# SArduino.net
KiCad netlist of a schematic drawn in EAGLE
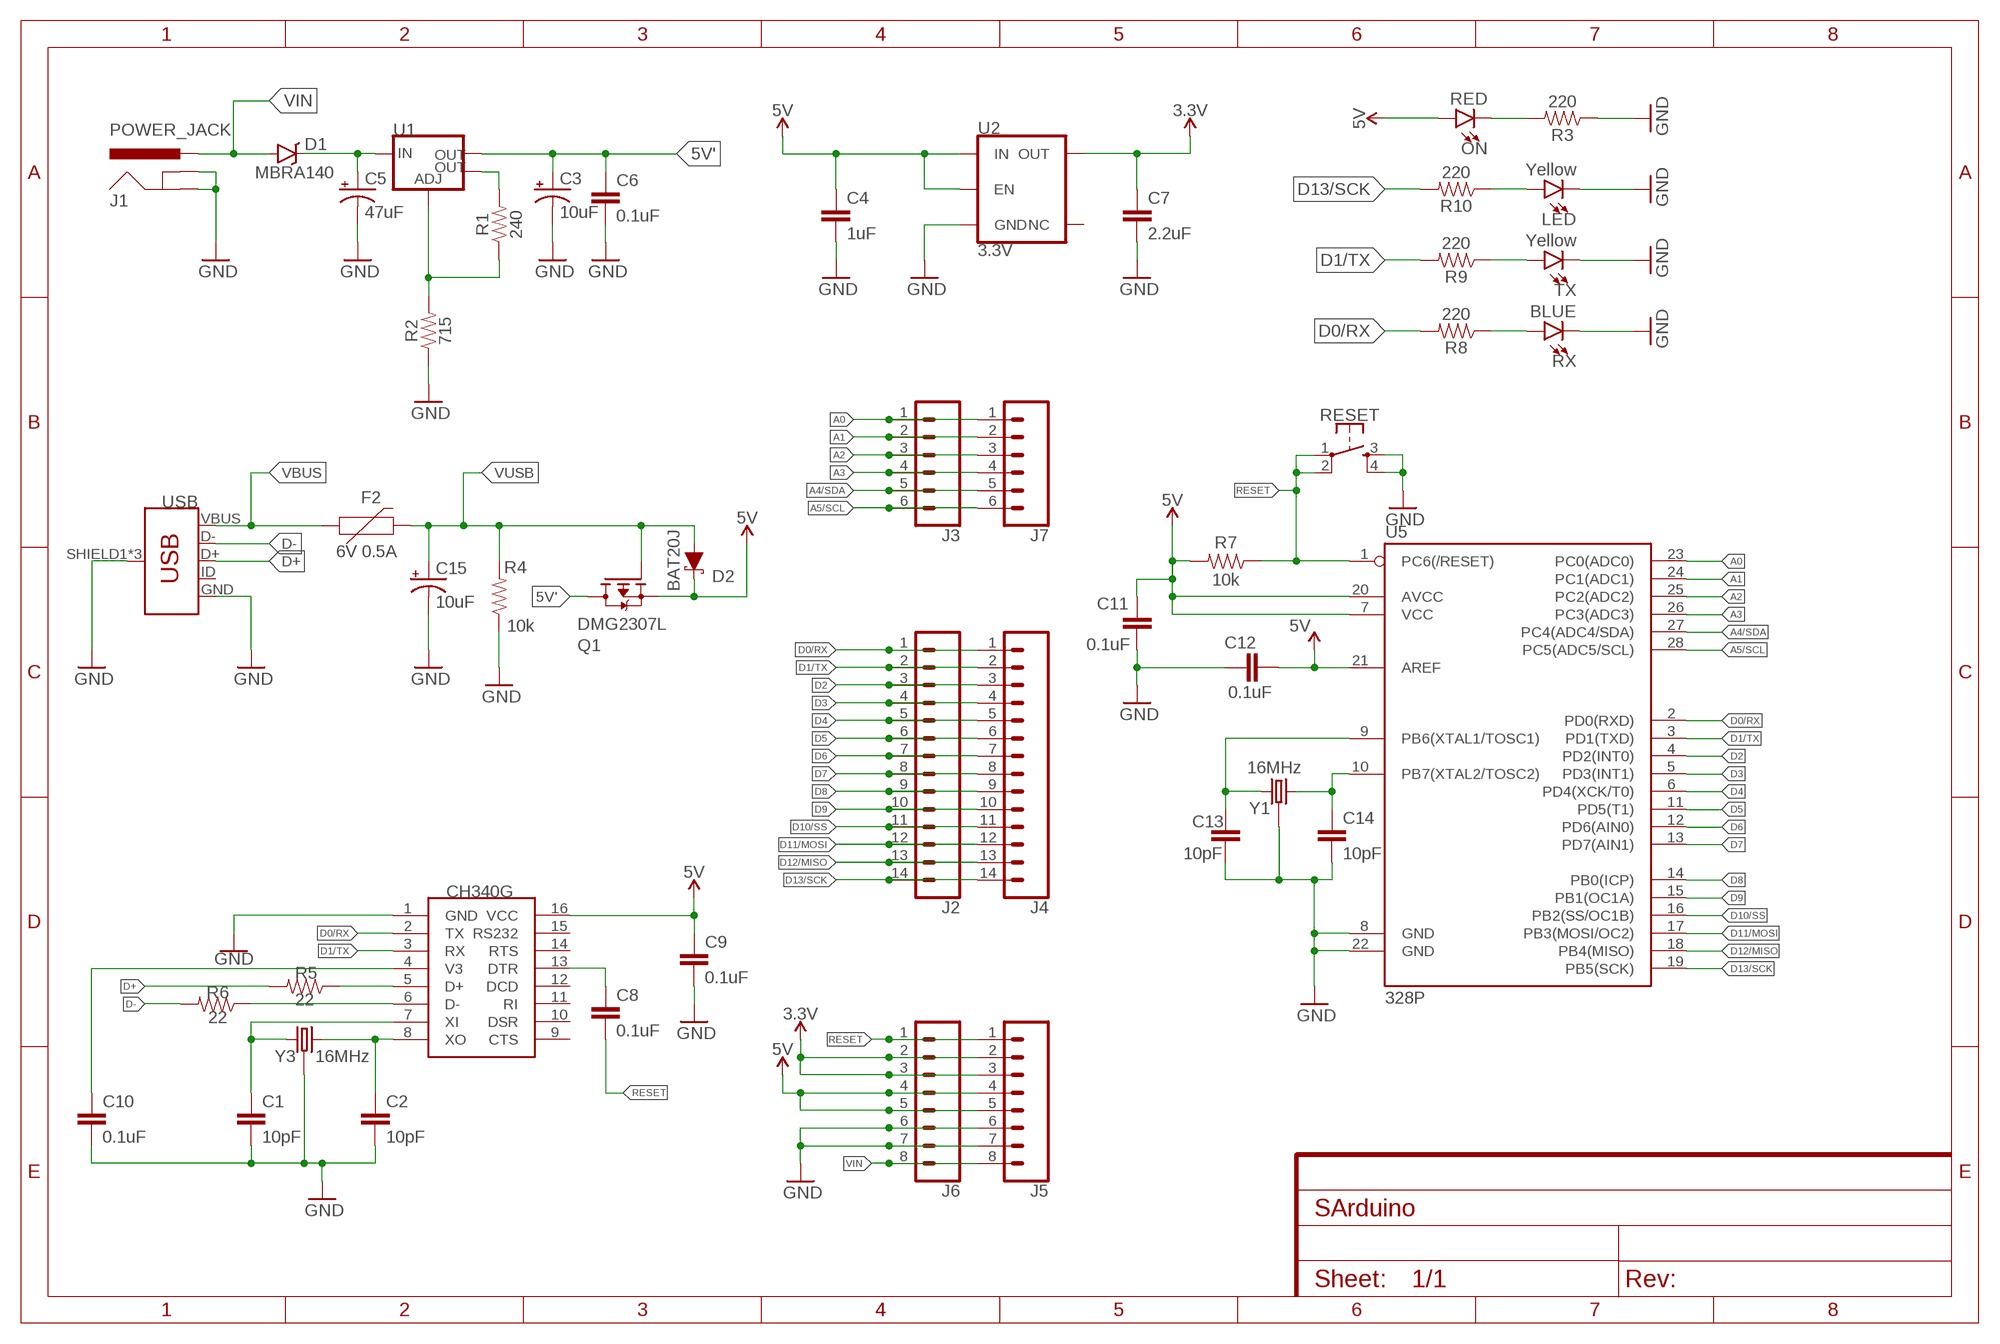
[diagram p0: schematic, sheet 1]

(export (version "E")
  (design (tool "Eeschema 10.0.6"))
  (components
    (comp (ref "C1")
      (value "10pF")
      (footprint "eagle-import:0603")
      (libsource (lib "eagle-import") (part "0.1UF-0603-25V-(+80/-20%)"))
    )
    (comp (ref "C2")
      (value "10pF")
      (footprint "eagle-import:0603")
      (libsource (lib "eagle-import") (part "0.1UF-0603-25V-(+80/-20%)"))
    )
    (comp (ref "C3")
      (value "10uF")
      (footprint "eagle-import:EIA3216")
      (libsource (lib "eagle-import") (part "10UF-POLAR-EIA3216-16V-10%(TANT)"))
    )
    (comp (ref "C4")
      (value "1uF")
      (footprint "eagle-import:0603")
      (libsource (lib "eagle-import") (part "0.1UF-0603-25V-(+80/-20%)"))
    )
    (comp (ref "C5")
      (value "47uF")
      (footprint "eagle-import:PANASONIC_D")
      (libsource (lib "eagle-import") (part "47UF-POLAR-PANASONIC_D-35V-20%"))
    )
    (comp (ref "C6")
      (value "0.1uF")
      (footprint "eagle-import:0603")
      (libsource (lib "eagle-import") (part "0.1UF-0603-25V-(+80/-20%)"))
    )
    (comp (ref "C7")
      (value "2.2uF")
      (footprint "eagle-import:0603")
      (libsource (lib "eagle-import") (part "0.1UF-0603-25V-(+80/-20%)"))
    )
    (comp (ref "C8")
      (value "0.1uF")
      (footprint "eagle-import:0603")
      (libsource (lib "eagle-import") (part "0.1UF-0603-25V-(+80/-20%)"))
    )
    (comp (ref "C9")
      (value "0.1uF")
      (footprint "eagle-import:0603")
      (libsource (lib "eagle-import") (part "0.1UF-0603-25V-(+80/-20%)"))
    )
    (comp (ref "C10")
      (value "0.1uF")
      (footprint "eagle-import:0603")
      (libsource (lib "eagle-import") (part "0.1UF-0603-25V-(+80/-20%)"))
    )
    (comp (ref "C11")
      (value "0.1uF")
      (footprint "eagle-import:0603")
      (libsource (lib "eagle-import") (part "0.1UF-0603-25V-(+80/-20%)"))
    )
    (comp (ref "C12")
      (value "0.1uF")
      (footprint "eagle-import:0603")
      (libsource (lib "eagle-import") (part "0.1UF-0603-25V-(+80/-20%)"))
    )
    (comp (ref "C13")
      (value "10pF")
      (footprint "eagle-import:0603")
      (libsource (lib "eagle-import") (part "0.1UF-0603-25V-(+80/-20%)"))
    )
    (comp (ref "C14")
      (value "10pF")
      (footprint "eagle-import:0603")
      (libsource (lib "eagle-import") (part "0.1UF-0603-25V-(+80/-20%)"))
    )
    (comp (ref "C15")
      (value "10uF")
      (footprint "eagle-import:EIA3216")
      (libsource (lib "eagle-import") (part "10UF-POLAR-EIA3216-16V-10%(TANT)"))
    )
    (comp (ref "D1")
      (value "MBRA140")
      (footprint "eagle-import:SMA-DIODE@1")
      (libsource (lib "eagle-import") (part "MBRA140"))
    )
    (comp (ref "D2")
      (value "BAT20J")
      (footprint "eagle-import:SOD-323")
      (libsource (lib "eagle-import") (part "DIODE-SCHOTTKY-BAT20J"))
    )
    (comp (ref "F2")
      (value "6V 0.5A")
      (footprint "eagle-import:0805")
      (libsource (lib "eagle-import") (part "PPTC_6V500MA"))
    )
    (comp (ref "J1")
      (value "POWER_JACK")
      (footprint "eagle-import:POWER_JACK_PTH")
      (libsource (lib "eagle-import") (part "POWER_JACK"))
    )
    (comp (ref "J2")
      (value "CONN_14")
      (footprint "eagle-import:1X14")
      (libsource (lib "eagle-import") (part "CONN_14"))
    )
    (comp (ref "J3")
      (value "CONN_06SILK_FEMALE_PTH")
      (footprint "eagle-import:1X06")
      (libsource (lib "eagle-import") (part "CONN_06SILK_FEMALE_PTH"))
    )
    (comp (ref "J4")
      (value "CONN_14")
      (footprint "eagle-import:1X14")
      (libsource (lib "eagle-import") (part "CONN_14"))
    )
    (comp (ref "J5")
      (value "CONN_08\"")
      (footprint "eagle-import:1X08")
      (libsource (lib "eagle-import") (part "CONN_08{dblquote}"))
    )
    (comp (ref "J6")
      (value "CONN_08\"")
      (footprint "eagle-import:1X08")
      (libsource (lib "eagle-import") (part "CONN_08{dblquote}"))
    )
    (comp (ref "J7")
      (value "CONN_06SILK_FEMALE_PTH")
      (footprint "eagle-import:1X06")
      (libsource (lib "eagle-import") (part "CONN_06SILK_FEMALE_PTH"))
    )
    (comp (ref "LED")
      (value "Yellow")
      (footprint "eagle-import:LED-0603")
      (libsource (lib "eagle-import") (part "LED-YELLOW0603"))
    )
    (comp (ref "ON")
      (value "RED")
      (footprint "eagle-import:LED-0603")
      (libsource (lib "eagle-import") (part "LED-RED0603"))
    )
    (comp (ref "Q1")
      (value "DMG2307L")
      (footprint "eagle-import:SOT96P240X110-3N")
      (fields (field (name "MF") "Diodes Inc."))
      (libsource (lib "eagle-import") (part "DMG2307L"))
    )
    (comp (ref "R1")
      (value "240")
      (footprint "eagle-import:0603")
      (libsource (lib "eagle-import") (part "240OHM-0603-1/10W-1%"))
    )
    (comp (ref "R2")
      (value "715")
      (footprint "eagle-import:0603")
      (libsource (lib "eagle-import") (part "715OHM-0603-1/10W-1%"))
    )
    (comp (ref "R3")
      (value "220")
      (footprint "eagle-import:0603")
      (libsource (lib "eagle-import") (part "240OHM-0603-1/10W-1%"))
    )
    (comp (ref "R4")
      (value "10k")
      (footprint "eagle-import:0603")
      (libsource (lib "eagle-import") (part "715OHM-0603-1/10W-1%"))
    )
    (comp (ref "R5")
      (value "22")
      (footprint "eagle-import:0603")
      (libsource (lib "eagle-import") (part "715OHM-0603-1/10W-1%"))
    )
    (comp (ref "R6")
      (value "22")
      (footprint "eagle-import:0603")
      (libsource (lib "eagle-import") (part "715OHM-0603-1/10W-1%"))
    )
    (comp (ref "R7")
      (value "10k")
      (footprint "eagle-import:0603")
      (libsource (lib "eagle-import") (part "715OHM-0603-1/10W-1%"))
    )
    (comp (ref "R8")
      (value "220")
      (footprint "eagle-import:0603")
      (libsource (lib "eagle-import") (part "240OHM-0603-1/10W-1%"))
    )
    (comp (ref "R9")
      (value "220")
      (footprint "eagle-import:0603")
      (libsource (lib "eagle-import") (part "240OHM-0603-1/10W-1%"))
    )
    (comp (ref "R10")
      (value "220")
      (footprint "eagle-import:0603")
      (libsource (lib "eagle-import") (part "240OHM-0603-1/10W-1%"))
    )
    (comp (ref "RESET")
      (value "MOMENTARY-SWITCH-SPST-2-SMD-5.2MM")
      (footprint "eagle-import:TACTILE_SWITCH_SMD_5.2MM")
      (libsource (lib "eagle-import") (part "MOMENTARY-SWITCH-SPST-2-SMD-5.2MM"))
    )
    (comp (ref "RX")
      (value "BLUE")
      (footprint "eagle-import:LED-0603")
      (libsource (lib "eagle-import") (part "LED-BLUE0603"))
    )
    (comp (ref "TX")
      (value "Yellow")
      (footprint "eagle-import:LED-0603")
      (libsource (lib "eagle-import") (part "LED-YELLOW0603"))
    )
    (comp (ref "U1")
      (value "V_REG_LM1117SOT223")
      (footprint "eagle-import:SOT223")
      (libsource (lib "eagle-import") (part "V_REG_LM1117SOT223"))
    )
    (comp (ref "U2")
      (value "3.3V")
      (footprint "eagle-import:SOT23-5")
      (libsource (lib "eagle-import") (part "V_REG_AP2112K-3.3V"))
    )
    (comp (ref "U3")
      (value "CH340G")
      (footprint "eagle-import:SOIC16")
      (libsource (lib "eagle-import") (part "CH340G"))
    )
    (comp (ref "U5")
      (value "328P")
      (footprint "eagle-import:DIP28")
      (libsource (lib "eagle-import") (part "ATMEGA328P_PDIP"))
    )
    (comp (ref "USB")
      (value "USB_MICRO-B_FEMALE-SMT")
      (footprint "eagle-import:USB-B-MICRO-SMD")
      (libsource (lib "eagle-import") (part "USB_MICRO-B_FEMALE-SMT"))
    )
    (comp (ref "Y1")
      (value "16MHz")
      (footprint "eagle-import:CRYSTAL-SMD-3.2X2.5MM")
      (libsource (lib "eagle-import") (part "CRYSTAL-GROUNDEDSMD-3.2X2.5"))
    )
    (comp (ref "Y3")
      (value "16MHz")
      (footprint "eagle-import:CRYSTAL-SMD-3.2X2.5MM")
      (libsource (lib "eagle-import") (part "CRYSTAL-GROUNDEDSMD-3.2X2.5"))
    )
  )
  (nets
    (net (code "1") (name "3.3V") (class "Default")
      (node (ref "C7") (pin "1") (pinfunction "1_1") (pintype "passive"))
      (node (ref "J5") (pin "2") (pinfunction "2_2") (pintype "passive"))
      (node (ref "J5") (pin "3") (pinfunction "3_3") (pintype "passive"))
      (node (ref "J6") (pin "2") (pinfunction "2_2") (pintype "passive"))
      (node (ref "J6") (pin "3") (pinfunction "3_3") (pintype "passive"))
      (node (ref "U2") (pin "5") (pinfunction "OUT_5") (pintype "passive"))
    )
    (net (code "2") (name "5V") (class "Default")
      (node (ref "C11") (pin "2") (pinfunction "2_2") (pintype "passive"))
      (node (ref "C12") (pin "2") (pinfunction "2_2") (pintype "passive"))
      (node (ref "C4") (pin "1") (pinfunction "1_1") (pintype "passive"))
      (node (ref "C9") (pin "1") (pinfunction "1_1") (pintype "passive"))
      (node (ref "D2") (pin "C") (pinfunction "C_C") (pintype "passive"))
      (node (ref "J5") (pin "4") (pinfunction "4_4") (pintype "passive"))
      (node (ref "J5") (pin "5") (pinfunction "5_5") (pintype "passive"))
      (node (ref "J6") (pin "4") (pinfunction "4_4") (pintype "passive"))
      (node (ref "J6") (pin "5") (pinfunction "5_5") (pintype "passive"))
      (node (ref "ON") (pin "A") (pinfunction "A_A") (pintype "passive"))
      (node (ref "Q1") (pin "2") (pinfunction "S_2") (pintype "passive"))
      (node (ref "R7") (pin "2") (pinfunction "2_2") (pintype "passive"))
      (node (ref "U2") (pin "1") (pinfunction "IN_1") (pintype "input"))
      (node (ref "U2") (pin "3") (pinfunction "EN_3") (pintype "input"))
      (node (ref "U3") (pin "16") (pinfunction "VCC_16") (pintype "bidirectional"))
      (node (ref "U5") (pin "20") (pinfunction "AVCC_20") (pintype "bidirectional"))
      (node (ref "U5") (pin "21") (pinfunction "AREF_21") (pintype "bidirectional"))
      (node (ref "U5") (pin "7") (pinfunction "VCC_7") (pintype "bidirectional"))
    )
    (net (code "3") (name "5V'") (class "Default")
      (node (ref "C3") (pin "+") (pinfunction "+_+") (pintype "passive"))
      (node (ref "C6") (pin "1") (pinfunction "1_1") (pintype "passive"))
      (node (ref "Q1") (pin "3") (pinfunction "D_3") (pintype "passive"))
      (node (ref "U1") (pin "2") (pinfunction "OUT_2") (pintype "output"))
    )
    (net (code "4") (name "A0") (class "Default")
      (node (ref "J3") (pin "1") (pinfunction "1_1") (pintype "passive"))
      (node (ref "J7") (pin "1") (pinfunction "1_1") (pintype "passive"))
      (node (ref "U5") (pin "23") (pinfunction "PC0(ADC0)_23") (pintype "bidirectional"))
    )
    (net (code "5") (name "A1") (class "Default")
      (node (ref "J3") (pin "2") (pinfunction "2_2") (pintype "passive"))
      (node (ref "J7") (pin "2") (pinfunction "2_2") (pintype "passive"))
      (node (ref "U5") (pin "24") (pinfunction "PC1(ADC1)_24") (pintype "bidirectional"))
    )
    (net (code "6") (name "A2") (class "Default")
      (node (ref "J3") (pin "3") (pinfunction "3_3") (pintype "passive"))
      (node (ref "J7") (pin "3") (pinfunction "3_3") (pintype "passive"))
      (node (ref "U5") (pin "25") (pinfunction "PC2(ADC2)_25") (pintype "bidirectional"))
    )
    (net (code "7") (name "A3") (class "Default")
      (node (ref "J3") (pin "4") (pinfunction "4_4") (pintype "passive"))
      (node (ref "J7") (pin "4") (pinfunction "4_4") (pintype "passive"))
      (node (ref "U5") (pin "26") (pinfunction "PC3(ADC3)_26") (pintype "bidirectional"))
    )
    (net (code "8") (name "A4{slash}SDA") (class "Default")
      (node (ref "J3") (pin "5") (pinfunction "5_5") (pintype "passive"))
      (node (ref "J7") (pin "5") (pinfunction "5_5") (pintype "passive"))
      (node (ref "U5") (pin "27") (pinfunction "PC4(ADC4/SDA)_27") (pintype "bidirectional"))
    )
    (net (code "9") (name "A5{slash}SCL") (class "Default")
      (node (ref "J3") (pin "6") (pinfunction "6_6") (pintype "passive"))
      (node (ref "J7") (pin "6") (pinfunction "6_6") (pintype "passive"))
      (node (ref "U5") (pin "28") (pinfunction "PC5(ADC5/SCL)_28") (pintype "bidirectional"))
    )
    (net (code "10") (name "D+") (class "Default")
      (node (ref "R5") (pin "2") (pinfunction "2_2") (pintype "passive"))
      (node (ref "USB") (pin "D+") (pinfunction "D+_D+") (pintype "bidirectional"))
    )
    (net (code "11") (name "D-") (class "Default")
      (node (ref "R6") (pin "2") (pinfunction "2_2") (pintype "passive"))
      (node (ref "USB") (pin "D-") (pinfunction "D-_D-") (pintype "bidirectional"))
    )
    (net (code "12") (name "D0{slash}RX") (class "Default")
      (node (ref "J2") (pin "1") (pinfunction "1_1") (pintype "passive"))
      (node (ref "J4") (pin "1") (pinfunction "1_1") (pintype "passive"))
      (node (ref "R8") (pin "2") (pinfunction "2_2") (pintype "passive"))
      (node (ref "U3") (pin "2") (pinfunction "TX_2") (pintype "bidirectional"))
      (node (ref "U5") (pin "2") (pinfunction "PD0(RXD)_2") (pintype "bidirectional"))
    )
    (net (code "13") (name "D1{slash}TX") (class "Default")
      (node (ref "J2") (pin "2") (pinfunction "2_2") (pintype "passive"))
      (node (ref "J4") (pin "2") (pinfunction "2_2") (pintype "passive"))
      (node (ref "R9") (pin "2") (pinfunction "2_2") (pintype "passive"))
      (node (ref "U3") (pin "3") (pinfunction "RX_3") (pintype "bidirectional"))
      (node (ref "U5") (pin "3") (pinfunction "PD1(TXD)_3") (pintype "bidirectional"))
    )
    (net (code "14") (name "D2") (class "Default")
      (node (ref "J2") (pin "3") (pinfunction "3_3") (pintype "passive"))
      (node (ref "J4") (pin "3") (pinfunction "3_3") (pintype "passive"))
      (node (ref "U5") (pin "4") (pinfunction "PD2(INT0)_4") (pintype "bidirectional"))
    )
    (net (code "15") (name "D3") (class "Default")
      (node (ref "J2") (pin "4") (pinfunction "4_4") (pintype "passive"))
      (node (ref "J4") (pin "4") (pinfunction "4_4") (pintype "passive"))
      (node (ref "U5") (pin "5") (pinfunction "PD3(INT1)_5") (pintype "bidirectional"))
    )
    (net (code "16") (name "D4") (class "Default")
      (node (ref "J2") (pin "5") (pinfunction "5_5") (pintype "passive"))
      (node (ref "J4") (pin "5") (pinfunction "5_5") (pintype "passive"))
      (node (ref "U5") (pin "6") (pinfunction "PD4(XCK/T0)_6") (pintype "bidirectional"))
    )
    (net (code "17") (name "D5") (class "Default")
      (node (ref "J2") (pin "6") (pinfunction "6_6") (pintype "passive"))
      (node (ref "J4") (pin "6") (pinfunction "6_6") (pintype "passive"))
      (node (ref "U5") (pin "11") (pinfunction "PD5(T1)_11") (pintype "bidirectional"))
    )
    (net (code "18") (name "D6") (class "Default")
      (node (ref "J2") (pin "7") (pinfunction "7_7") (pintype "passive"))
      (node (ref "J4") (pin "7") (pinfunction "7_7") (pintype "passive"))
      (node (ref "U5") (pin "12") (pinfunction "PD6(AIN0)_12") (pintype "bidirectional"))
    )
    (net (code "19") (name "D7") (class "Default")
      (node (ref "J2") (pin "8") (pinfunction "8_8") (pintype "passive"))
      (node (ref "J4") (pin "8") (pinfunction "8_8") (pintype "passive"))
      (node (ref "U5") (pin "13") (pinfunction "PD7(AIN1)_13") (pintype "bidirectional"))
    )
    (net (code "20") (name "D8") (class "Default")
      (node (ref "J2") (pin "9") (pinfunction "9_9") (pintype "passive"))
      (node (ref "J4") (pin "9") (pinfunction "9_9") (pintype "passive"))
      (node (ref "U5") (pin "14") (pinfunction "PB0(ICP)_14") (pintype "bidirectional"))
    )
    (net (code "21") (name "D9") (class "Default")
      (node (ref "J2") (pin "10") (pinfunction "10_10") (pintype "passive"))
      (node (ref "J4") (pin "10") (pinfunction "10_10") (pintype "passive"))
      (node (ref "U5") (pin "15") (pinfunction "PB1(OC1A)_15") (pintype "bidirectional"))
    )
    (net (code "22") (name "D10{slash}SS") (class "Default")
      (node (ref "J2") (pin "11") (pinfunction "11_11") (pintype "passive"))
      (node (ref "J4") (pin "11") (pinfunction "11_11") (pintype "passive"))
      (node (ref "U5") (pin "16") (pinfunction "PB2(SS/OC1B)_16") (pintype "bidirectional"))
    )
    (net (code "23") (name "D11{slash}MOSI") (class "Default")
      (node (ref "J2") (pin "12") (pinfunction "12_12") (pintype "passive"))
      (node (ref "J4") (pin "12") (pinfunction "12_12") (pintype "passive"))
      (node (ref "U5") (pin "17") (pinfunction "PB3(MOSI/OC2)_17") (pintype "bidirectional"))
    )
    (net (code "24") (name "D12{slash}MISO") (class "Default")
      (node (ref "J2") (pin "13") (pinfunction "13_13") (pintype "passive"))
      (node (ref "J4") (pin "13") (pinfunction "13_13") (pintype "passive"))
      (node (ref "U5") (pin "18") (pinfunction "PB4(MISO)_18") (pintype "bidirectional"))
    )
    (net (code "25") (name "D13{slash}SCK") (class "Default")
      (node (ref "J2") (pin "14") (pinfunction "14_14") (pintype "passive"))
      (node (ref "J4") (pin "14") (pinfunction "14_14") (pintype "passive"))
      (node (ref "R10") (pin "2") (pinfunction "2_2") (pintype "passive"))
      (node (ref "U5") (pin "19") (pinfunction "PB5(SCK)_19") (pintype "bidirectional"))
    )
    (net (code "26") (name "GND") (class "Default")
      (node (ref "C1") (pin "2") (pinfunction "2_2") (pintype "passive"))
      (node (ref "C10") (pin "2") (pinfunction "2_2") (pintype "passive"))
      (node (ref "C11") (pin "1") (pinfunction "1_1") (pintype "passive"))
      (node (ref "C12") (pin "1") (pinfunction "1_1") (pintype "passive"))
      (node (ref "C13") (pin "2") (pinfunction "2_2") (pintype "passive"))
      (node (ref "C14") (pin "2") (pinfunction "2_2") (pintype "passive"))
      (node (ref "C15") (pin "-") (pinfunction "-_-") (pintype "passive"))
      (node (ref "C2") (pin "2") (pinfunction "2_2") (pintype "passive"))
      (node (ref "C3") (pin "-") (pinfunction "-_-") (pintype "passive"))
      (node (ref "C4") (pin "2") (pinfunction "2_2") (pintype "passive"))
      (node (ref "C5") (pin "-") (pinfunction "-_-") (pintype "passive"))
      (node (ref "C6") (pin "2") (pinfunction "2_2") (pintype "passive"))
      (node (ref "C7") (pin "2") (pinfunction "2_2") (pintype "passive"))
      (node (ref "C9") (pin "2") (pinfunction "2_2") (pintype "passive"))
      (node (ref "J1") (pin "GND") (pinfunction "GND_GND") (pintype "bidirectional"))
      (node (ref "J1") (pin "GNDBREAK") (pinfunction "GNDBREAK_GNDBREAK") (pintype "bidirectional"))
      (node (ref "J5") (pin "6") (pinfunction "6_6") (pintype "passive"))
      (node (ref "J5") (pin "7") (pinfunction "7_7") (pintype "passive"))
      (node (ref "J6") (pin "6") (pinfunction "6_6") (pintype "passive"))
      (node (ref "J6") (pin "7") (pinfunction "7_7") (pintype "passive"))
      (node (ref "LED") (pin "C") (pinfunction "C_C") (pintype "passive"))
      (node (ref "R2") (pin "1") (pinfunction "1_1") (pintype "passive"))
      (node (ref "R3") (pin "1") (pinfunction "1_1") (pintype "passive"))
      (node (ref "R4") (pin "1") (pinfunction "1_1") (pintype "passive"))
      (node (ref "RESET") (pin "3") (pinfunction "3_3") (pintype "passive"))
      (node (ref "RESET") (pin "4") (pinfunction "4_4") (pintype "passive"))
      (node (ref "RX") (pin "C") (pinfunction "C_C") (pintype "passive"))
      (node (ref "TX") (pin "C") (pinfunction "C_C") (pintype "passive"))
      (node (ref "U2") (pin "2") (pinfunction "GND_2") (pintype "input"))
      (node (ref "U3") (pin "1") (pinfunction "GND_1") (pintype "bidirectional"))
      (node (ref "U5") (pin "22") (pinfunction "GND_22") (pintype "bidirectional"))
      (node (ref "U5") (pin "8") (pinfunction "GND_8") (pintype "bidirectional"))
      (node (ref "USB") (pin "GND") (pinfunction "GND_GND") (pintype "power_in"))
      (node (ref "USB") (pin "SHIELD1") (pinfunction "SHIELD_SHIELD1") (pintype "bidirectional"))
      (node (ref "USB") (pin "SHIELD2") (pinfunction "SHIELD_SHIELD2") (pintype "bidirectional"))
      (node (ref "USB") (pin "SHIELD3") (pinfunction "SHIELD_SHIELD3") (pintype "bidirectional"))
      (node (ref "Y1") (pin "2") (pinfunction "GND_2") (pintype "power_in"))
      (node (ref "Y1") (pin "4") (pinfunction "GND_4") (pintype "power_in"))
      (node (ref "Y3") (pin "2") (pinfunction "GND_2") (pintype "power_in"))
      (node (ref "Y3") (pin "4") (pinfunction "GND_4") (pintype "power_in"))
    )
    (net (code "27") (name "Net-(LED-PadA)") (class "Default")
      (node (ref "LED") (pin "A") (pinfunction "A_A") (pintype "passive"))
      (node (ref "R10") (pin "1") (pinfunction "1_1") (pintype "passive"))
    )
    (net (code "28") (name "Net-(ON-PadC)") (class "Default")
      (node (ref "ON") (pin "C") (pinfunction "C_C") (pintype "passive"))
      (node (ref "R3") (pin "2") (pinfunction "2_2") (pintype "passive"))
    )
    (net (code "29") (name "Net-(R1-Pad2)") (class "Default")
      (node (ref "R1") (pin "2") (pinfunction "2_2") (pintype "passive"))
      (node (ref "U1") (pin "4") (pinfunction "OUT_4") (pintype "output"))
    )
    (net (code "30") (name "Net-(R8-Pad1)") (class "Default")
      (node (ref "R8") (pin "1") (pinfunction "1_1") (pintype "passive"))
      (node (ref "RX") (pin "A") (pinfunction "A_A") (pintype "passive"))
    )
    (net (code "31") (name "Net-(R9-Pad1)") (class "Default")
      (node (ref "R9") (pin "1") (pinfunction "1_1") (pintype "passive"))
      (node (ref "TX") (pin "A") (pinfunction "A_A") (pintype "passive"))
    )
    (net (code "32") (name "Net-(U1-ADJ)") (class "Default")
      (node (ref "R1") (pin "1") (pinfunction "1_1") (pintype "passive"))
      (node (ref "R2") (pin "2") (pinfunction "2_2") (pintype "passive"))
      (node (ref "U1") (pin "1") (pinfunction "ADJ_1") (pintype "input"))
    )
    (net (code "33") (name "Net-(U1-IN)") (class "Default")
      (node (ref "C5") (pin "+") (pinfunction "+_+") (pintype "passive"))
      (node (ref "D1") (pin "C") (pinfunction "C_C") (pintype "passive"))
      (node (ref "U1") (pin "3") (pinfunction "IN_3") (pintype "input"))
    )
    (net (code "34") (name "Net-(U3-D+)") (class "Default")
      (node (ref "R5") (pin "1") (pinfunction "1_1") (pintype "passive"))
      (node (ref "U3") (pin "5") (pinfunction "D+_5") (pintype "bidirectional"))
    )
    (net (code "35") (name "Net-(U3-D-)") (class "Default")
      (node (ref "R6") (pin "1") (pinfunction "1_1") (pintype "passive"))
      (node (ref "U3") (pin "6") (pinfunction "D-_6") (pintype "bidirectional"))
    )
    (net (code "36") (name "Net-(U3-DTR)") (class "Default")
      (node (ref "C8") (pin "1") (pinfunction "1_1") (pintype "passive"))
      (node (ref "U3") (pin "13") (pinfunction "DTR_13") (pintype "bidirectional"))
    )
    (net (code "37") (name "Net-(U3-V3)") (class "Default")
      (node (ref "C10") (pin "1") (pinfunction "1_1") (pintype "passive"))
      (node (ref "U3") (pin "4") (pinfunction "V3_4") (pintype "bidirectional"))
    )
    (net (code "38") (name "Net-(U3-XI)") (class "Default")
      (node (ref "C1") (pin "1") (pinfunction "1_1") (pintype "passive"))
      (node (ref "U3") (pin "7") (pinfunction "XI_7") (pintype "bidirectional"))
      (node (ref "Y3") (pin "1") (pinfunction "1_1") (pintype "passive"))
    )
    (net (code "39") (name "Net-(U3-XO)") (class "Default")
      (node (ref "C2") (pin "1") (pinfunction "1_1") (pintype "passive"))
      (node (ref "U3") (pin "8") (pinfunction "XO_8") (pintype "bidirectional"))
      (node (ref "Y3") (pin "3") (pinfunction "2_3") (pintype "passive"))
    )
    (net (code "40") (name "Net-(U5-PB6(XTAL1{slash}TOSC1))") (class "Default")
      (node (ref "C13") (pin "1") (pinfunction "1_1") (pintype "passive"))
      (node (ref "U5") (pin "9") (pinfunction "PB6(XTAL1/TOSC1)_9") (pintype "bidirectional"))
      (node (ref "Y1") (pin "1") (pinfunction "1_1") (pintype "passive"))
    )
    (net (code "41") (name "Net-(U5-PB7(XTAL2{slash}TOSC2))") (class "Default")
      (node (ref "C14") (pin "1") (pinfunction "1_1") (pintype "passive"))
      (node (ref "U5") (pin "10") (pinfunction "PB7(XTAL2/TOSC2)_10") (pintype "bidirectional"))
      (node (ref "Y1") (pin "3") (pinfunction "2_3") (pintype "passive"))
    )
    (net (code "42") (name "RESET") (class "Default")
      (node (ref "C8") (pin "2") (pinfunction "2_2") (pintype "passive"))
      (node (ref "J5") (pin "1") (pinfunction "1_1") (pintype "passive"))
      (node (ref "J6") (pin "1") (pinfunction "1_1") (pintype "passive"))
      (node (ref "R7") (pin "1") (pinfunction "1_1") (pintype "passive"))
      (node (ref "RESET") (pin "1") (pinfunction "1_1") (pintype "passive"))
      (node (ref "RESET") (pin "2") (pinfunction "2_2") (pintype "passive"))
      (node (ref "U5") (pin "1") (pinfunction "PC6(/RESET)_1") (pintype "bidirectional"))
    )
    (net (code "43") (name "VBUS") (class "Default")
      (node (ref "F2") (pin "1") (pinfunction "1_1") (pintype "bidirectional"))
      (node (ref "USB") (pin "VBUS") (pinfunction "VBUS_VBUS") (pintype "power_in"))
    )
    (net (code "44") (name "VIN") (class "Default")
      (node (ref "D1") (pin "A") (pinfunction "A_A") (pintype "passive"))
      (node (ref "J1") (pin "PWR") (pinfunction "PWR_PWR") (pintype "bidirectional"))
      (node (ref "J5") (pin "8") (pinfunction "8_8") (pintype "passive"))
      (node (ref "J6") (pin "8") (pinfunction "8_8") (pintype "passive"))
    )
    (net (code "45") (name "VUSB") (class "Default")
      (node (ref "C15") (pin "+") (pinfunction "+_+") (pintype "passive"))
      (node (ref "D2") (pin "A") (pinfunction "A_A") (pintype "passive"))
      (node (ref "F2") (pin "2") (pinfunction "2_2") (pintype "bidirectional"))
      (node (ref "Q1") (pin "1") (pinfunction "G_1") (pintype "passive"))
      (node (ref "R4") (pin "2") (pinfunction "2_2") (pintype "passive"))
    )
    (net (code "46") (name "unconnected-(U2-NC-Pad4)") (class "Default")
      (node (ref "U2") (pin "4") (pinfunction "NC_4") (pintype "no_connect"))
    )
    (net (code "47") (name "unconnected-(U3-CTS-Pad9)") (class "Default")
      (node (ref "U3") (pin "9") (pinfunction "CTS_9") (pintype "bidirectional"))
    )
    (net (code "48") (name "unconnected-(U3-DCD-Pad12)") (class "Default")
      (node (ref "U3") (pin "12") (pinfunction "DCD_12") (pintype "bidirectional"))
    )
    (net (code "49") (name "unconnected-(U3-DSR-Pad10)") (class "Default")
      (node (ref "U3") (pin "10") (pinfunction "DSR_10") (pintype "bidirectional"))
    )
    (net (code "50") (name "unconnected-(U3-RI-Pad11)") (class "Default")
      (node (ref "U3") (pin "11") (pinfunction "RI_11") (pintype "bidirectional"))
    )
    (net (code "51") (name "unconnected-(U3-RS232-Pad15)") (class "Default")
      (node (ref "U3") (pin "15") (pinfunction "RS232_15") (pintype "bidirectional"))
    )
    (net (code "52") (name "unconnected-(U3-RTS-Pad14)") (class "Default")
      (node (ref "U3") (pin "14") (pinfunction "RTS_14") (pintype "bidirectional"))
    )
    (net (code "53") (name "unconnected-(USB-PadID)") (class "Default")
      (node (ref "USB") (pin "ID") (pinfunction "ID_ID") (pintype "bidirectional"))
    )
  )
)
